# EM78P510_EM198810.net
KiCad netlist of a schematic drawn in Altium Designer
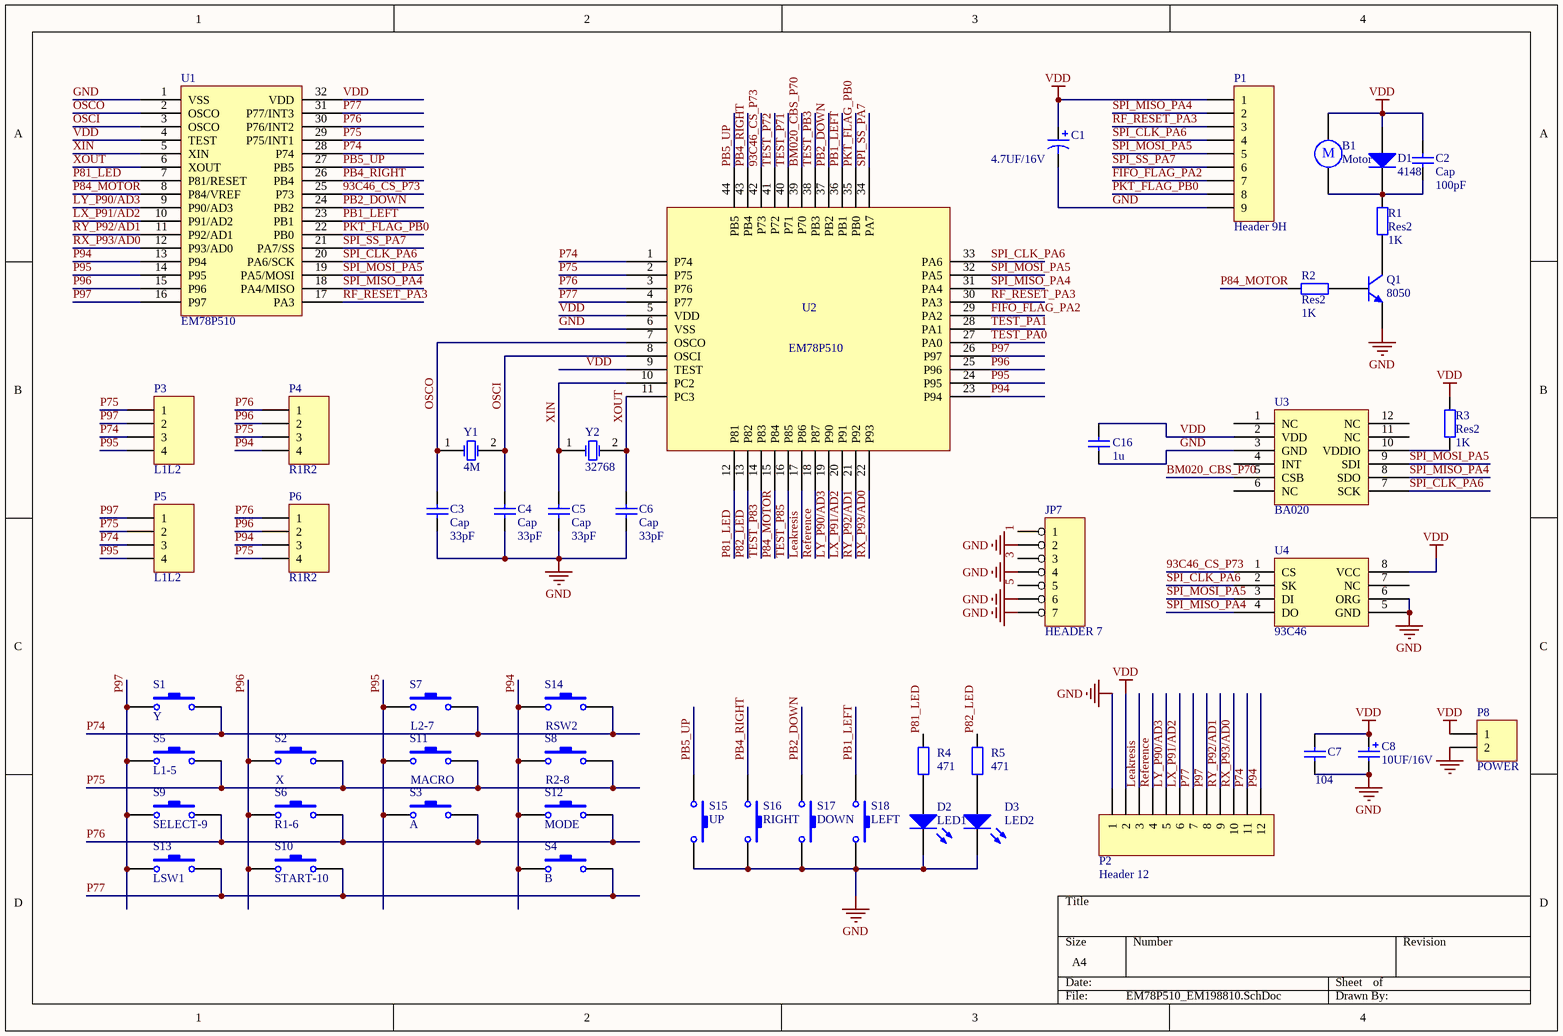
[diagram p0: EM78P510_EM198810.SchDoc]

(export (version "E")
  (design (tool "Eeschema 10.0.6"))
  (components
    (comp (ref "B1")
      (value "Motor")
      (footprint "sip2")
      (description "Motor, General Kind")
      (fields (field (name "PUBLISHER") "Altium Limited"))
      (libsource (lib "Miscellaneous Devices") (part "Motor"))
    )
    (comp (ref "C1")
      (value "4.7UF/16V")
      (footprint "c1206-2")
      (description "Polarized Capacitor (Radial)")
      (fields (field (name "Comment") "Cap Pol1") (field (name "PUBLISHER") "Altium Limited"))
      (libsource (lib "Miscellaneous Devices") (part "Cap Pol1"))
    )
    (comp (ref "C2")
      (value "Cap")
      (footprint "c0805")
      (description "Capacitor")
      (fields (field (name "ALTIUM_VALUE") "100pF") (field (name "PUBLISHER") "Altium Limited"))
      (libsource (lib "Miscellaneous Devices") (part "Cap"))
    )
    (comp (ref "C3")
      (value "Cap")
      (footprint "c0805")
      (description "Capacitor")
      (fields (field (name "ALTIUM_VALUE") "33pF") (field (name "PUBLISHER") "Altium Limited"))
      (libsource (lib "Miscellaneous Devices") (part "Cap"))
    )
    (comp (ref "C4")
      (value "Cap")
      (footprint "c0805")
      (description "Capacitor")
      (fields (field (name "ALTIUM_VALUE") "33pF") (field (name "PUBLISHER") "Altium Limited"))
      (libsource (lib "Miscellaneous Devices") (part "Cap"))
    )
    (comp (ref "C5")
      (value "Cap")
      (footprint "c0805")
      (description "Capacitor")
      (fields (field (name "ALTIUM_VALUE") "33pF") (field (name "PUBLISHER") "Altium Limited"))
      (libsource (lib "Miscellaneous Devices") (part "Cap"))
    )
    (comp (ref "C6")
      (value "Cap")
      (footprint "c0805")
      (description "Capacitor")
      (fields (field (name "ALTIUM_VALUE") "33pF") (field (name "PUBLISHER") "Altium Limited"))
      (libsource (lib "Miscellaneous Devices") (part "Cap"))
    )
    (comp (ref "C7")
      (value "104")
      (footprint "C0805")
      (description "Capacitor")
      (fields (field (name "Comment") "Cap") (field (name "PUBLISHER") "Altium Limited"))
      (libsource (lib "Miscellaneous Devices") (part "Cap"))
    )
    (comp (ref "C8")
      (value "10UF/16V")
      (footprint "RB5")
      (description "Polarized Capacitor (Radial)")
      (fields (field (name "Comment") "Cap Pol1") (field (name "PUBLISHER") "Altium Limited"))
      (libsource (lib "EM78P510_EM78M611_EM198810") (part "Cap Pol1"))
    )
    (comp (ref "C16")
      (value "1u")
      (footprint "C0805")
      (description "Capacitor")
      (fields (field (name "Comment") "Cap") (field (name "PUBLISHER") "Altium Limited"))
      (libsource (lib "Miscellaneous Devices") (part "Cap"))
    )
    (comp (ref "D1")
      (value "4148")
      (footprint "d1407")
      (description "Default Diode")
      (fields (field (name "PUBLISHER") "Altium Limited"))
      (libsource (lib "Miscellaneous Devices") (part "Diode"))
    )
    (comp (ref "D2")
      (value "LED1")
      (footprint "led-3")
      (description "Typical INFRARED GaAs LED")
      (fields (field (name "PUBLISHER") "Altium Limited"))
      (libsource (lib "Miscellaneous Devices") (part "LED0"))
    )
    (comp (ref "D3")
      (value "LED2")
      (footprint "led-3")
      (description "Typical INFRARED GaAs LED")
      (fields (field (name "PUBLISHER") "Altium Limited"))
      (libsource (lib "Miscellaneous Devices") (part "LED0"))
    )
    (comp (ref "JP7") (value "HEADER 7") (footprint "CON5") (libsource (lib "雨点元件") (part "HEADER 7")))
    (comp (ref "P1")
      (value "Header 9H")
      (footprint "rfm")
      (description "Header, 9-Pin, Right Angle")
      (fields (field (name "PUBLISHER") "Altium Limited"))
      (libsource (lib "Miscellaneous Connectors") (part "Header 9H"))
    )
    (comp (ref "P2")
      (value "Header 12")
      (footprint "SIP12")
      (description "Header, 12-Pin")
      (fields (field (name "PUBLISHER") "Altium Limited"))
      (libsource (lib "Miscellaneous Connectors") (part "Header 12"))
    )
    (comp (ref "P3")
      (value "L1L2")
      (footprint "SIP4")
      (description "Header, 4-Pin")
      (fields (field (name "PUBLISHER") "Altium Limited"))
      (libsource (lib "Miscellaneous Connectors") (part "Header 4"))
    )
    (comp (ref "P4")
      (value "R1R2")
      (footprint "SIP4")
      (description "Header, 4-Pin")
      (fields (field (name "PUBLISHER") "Altium Limited"))
      (libsource (lib "Miscellaneous Connectors") (part "Header 4"))
    )
    (comp (ref "P5")
      (value "L1L2")
      (footprint "SIP4")
      (description "Header, 4-Pin")
      (fields (field (name "PUBLISHER") "Altium Limited"))
      (libsource (lib "Miscellaneous Connectors") (part "Header 4"))
    )
    (comp (ref "P6")
      (value "R1R2")
      (footprint "SIP4")
      (description "Header, 4-Pin")
      (fields (field (name "PUBLISHER") "Altium Limited"))
      (libsource (lib "Miscellaneous Connectors") (part "Header 4"))
    )
    (comp (ref "P8")
      (value "POWER")
      (footprint "SIP2")
      (description "Header, 2-Pin")
      (fields (field (name "PUBLISHER") "Altium Limited"))
      (libsource (lib "Miscellaneous Connectors") (part "Header 2"))
    )
    (comp (ref "Q1")
      (value "8050")
      (footprint "sot-23")
      (description "NPN Bipolar Transistor")
      (fields (field (name "PUBLISHER") "Altium Limited"))
      (libsource (lib "Miscellaneous Devices") (part "NPN"))
    )
    (comp (ref "R1")
      (value "Res2")
      (footprint "r0805")
      (description "Resistor")
      (fields (field (name "ALTIUM_VALUE") "1K") (field (name "PUBLISHER") "Altium Limited"))
      (libsource (lib "Miscellaneous Devices") (part "Res2"))
    )
    (comp (ref "R2")
      (value "Res2")
      (footprint "r0805")
      (description "Resistor")
      (fields (field (name "ALTIUM_VALUE") "1K") (field (name "PUBLISHER") "Altium Limited"))
      (libsource (lib "") (part "Res2_1"))
    )
    (comp (ref "R3")
      (value "Res2")
      (footprint "r0805")
      (description "Resistor")
      (fields (field (name "ALTIUM_VALUE") "1K") (field (name "PUBLISHER") "Altium Limited"))
      (libsource (lib "Miscellaneous Devices") (part "Res2"))
    )
    (comp (ref "R4")
      (value "471")
      (footprint "r0805")
      (description "Resistor")
      (fields (field (name "Comment") "Res2") (field (name "PUBLISHER") "Altium Limited"))
      (libsource (lib "Miscellaneous Devices") (part "Res2"))
    )
    (comp (ref "R5")
      (value "471")
      (footprint "r0805")
      (description "Resistor")
      (fields (field (name "Comment") "Res2") (field (name "PUBLISHER") "Altium Limited"))
      (libsource (lib "Miscellaneous Devices") (part "Res2"))
    )
    (comp (ref "S1")
      (value "Y")
      (footprint "KeyPad1")
      (description "Switch")
      (fields (field (name "PUBLISHER") "Altium Limited"))
      (libsource (lib "EM78P510_EM78M611_EM198810_1") (part "SW-PB"))
    )
    (comp (ref "S2")
      (value "X")
      (footprint "KeyPad1")
      (description "Switch")
      (fields (field (name "PUBLISHER") "Altium Limited"))
      (libsource (lib "EM78P510_EM78M611_EM198810_1") (part "SW-PB"))
    )
    (comp (ref "S3")
      (value "A")
      (footprint "KeyPad1")
      (description "Switch")
      (fields (field (name "PUBLISHER") "Altium Limited"))
      (libsource (lib "EM78P510_EM78M611_EM198810_1") (part "SW-PB"))
    )
    (comp (ref "S4")
      (value "B")
      (footprint "KeyPad1")
      (description "Switch")
      (fields (field (name "PUBLISHER") "Altium Limited"))
      (libsource (lib "EM78P510_EM78M611_EM198810_1") (part "SW-PB"))
    )
    (comp (ref "S5")
      (value "L1-5")
      (footprint "KeyPad1")
      (description "Switch")
      (fields (field (name "PUBLISHER") "Altium Limited"))
      (libsource (lib "EM78P510_EM78M611_EM198810_1") (part "SW-PB"))
    )
    (comp (ref "S6")
      (value "R1-6")
      (footprint "KeyPad1")
      (description "Switch")
      (fields (field (name "PUBLISHER") "Altium Limited"))
      (libsource (lib "EM78P510_EM78M611_EM198810_1") (part "SW-PB"))
    )
    (comp (ref "S7")
      (value "L2-7")
      (footprint "KeyPad1")
      (description "Switch")
      (fields (field (name "PUBLISHER") "Altium Limited"))
      (libsource (lib "EM78P510_EM78M611_EM198810_1") (part "SW-PB"))
    )
    (comp (ref "S8")
      (value "R2-8")
      (footprint "KeyPad1")
      (description "Switch")
      (fields (field (name "PUBLISHER") "Altium Limited"))
      (libsource (lib "EM78P510_EM78M611_EM198810_1") (part "SW-PB"))
    )
    (comp (ref "S9")
      (value "SELECT-9")
      (footprint "KeyPad2")
      (description "Switch")
      (fields (field (name "PUBLISHER") "Altium Limited"))
      (libsource (lib "EM78P510_EM78M611_EM198810_1") (part "SW-PB"))
    )
    (comp (ref "S10")
      (value "START-10")
      (footprint "KeyPad2")
      (description "Switch")
      (fields (field (name "PUBLISHER") "Altium Limited"))
      (libsource (lib "EM78P510_EM78M611_EM198810_1") (part "SW-PB"))
    )
    (comp (ref "S11")
      (value "MACRO")
      (footprint "KeyPad2")
      (description "Switch")
      (fields (field (name "PUBLISHER") "Altium Limited"))
      (libsource (lib "EM78P510_EM78M611_EM198810_1") (part "SW-PB"))
    )
    (comp (ref "S12")
      (value "MODE")
      (footprint "KeyPad2")
      (description "Switch")
      (fields (field (name "PUBLISHER") "Altium Limited"))
      (libsource (lib "EM78P510_EM78M611_EM198810_1") (part "SW-PB"))
    )
    (comp (ref "S13")
      (value "LSW1")
      (footprint "KeyPad1")
      (description "Switch")
      (fields (field (name "PUBLISHER") "Altium Limited"))
      (libsource (lib "EM78P510_EM78M611_EM198810_1") (part "SW-PB"))
    )
    (comp (ref "S14")
      (value "RSW2")
      (footprint "KeyPad1")
      (description "Switch")
      (fields (field (name "PUBLISHER") "Altium Limited"))
      (libsource (lib "EM78P510_EM78M611_EM198810_1") (part "SW-PB"))
    )
    (comp (ref "S15")
      (value "UP")
      (footprint "KeyPad1")
      (description "Switch")
      (fields (field (name "PUBLISHER") "Altium Limited"))
      (libsource (lib "EM78P510_EM78M611_EM198810_1") (part "SW-PB"))
    )
    (comp (ref "S16")
      (value "RIGHT")
      (footprint "KeyPad1")
      (description "Switch")
      (fields (field (name "PUBLISHER") "Altium Limited"))
      (libsource (lib "EM78P510_EM78M611_EM198810_1") (part "SW-PB"))
    )
    (comp (ref "S17")
      (value "DOWN")
      (footprint "KeyPad1")
      (description "Switch")
      (fields (field (name "PUBLISHER") "Altium Limited"))
      (libsource (lib "EM78P510_EM78M611_EM198810_1") (part "SW-PB"))
    )
    (comp (ref "S18")
      (value "LEFT")
      (footprint "KeyPad1")
      (description "Switch")
      (fields (field (name "PUBLISHER") "Altium Limited"))
      (libsource (lib "EM78P510_EM78M611_EM198810_1") (part "SW-PB"))
    )
    (comp (ref "U1") (value "EM78P510") (libsource (lib "Schlib1") (part "EM78P510-32")))
    (comp (ref "U2") (value "EM78P510") (libsource (lib "Schlib1") (part "EM78P510-44")))
    (comp (ref "U3") (value "BA020") (footprint "lcc12") (libsource (lib "Schlib1") (part "BA020")))
    (comp (ref "U4") (value "93C46") (footprint "sop8") (libsource (lib "Schlib1") (part "93C46")))
    (comp (ref "Y1")
      (value "4M")
      (footprint "XTAL1")
      (description "Crystal Oscillator")
      (fields (field (name "PUBLISHER") "Altium Limited"))
      (libsource (lib "Miscellaneous Devices") (part "XTAL"))
    )
    (comp (ref "Y2")
      (value "32768")
      (footprint "XTAL2")
      (description "Crystal Oscillator")
      (fields (field (name "PUBLISHER") "Altium Limited"))
      (libsource (lib "Miscellaneous Devices") (part "XTAL"))
    )
  )
  (nets
    (net (code "1") (name "/1") (class "Default")
      (node (ref "JP7") (pin "1") (pinfunction "1_1") (pintype "passive"))
    )
    (net (code "2") (name "/3") (class "Default")
      (node (ref "JP7") (pin "3") (pinfunction "3_3") (pintype "passive"))
    )
    (net (code "3") (name "/5") (class "Default")
      (node (ref "JP7") (pin "5") (pinfunction "5_5") (pintype "passive"))
    )
    (net (code "4") (name "/93C46_CS_P73") (class "Default")
      (node (ref "U1") (pin "25") (pinfunction "P73_25") (pintype "passive"))
      (node (ref "U2") (pin "42") (pinfunction "P73_42") (pintype "passive"))
      (node (ref "U4") (pin "1") (pinfunction "CS_1") (pintype "passive"))
    )
    (net (code "5") (name "/BM020_CBS_P70") (class "Default")
      (node (ref "U2") (pin "39") (pinfunction "P70_39") (pintype "passive"))
      (node (ref "U3") (pin "5") (pinfunction "CSB_5") (pintype "passive"))
    )
    (net (code "6") (name "/FIFO_FLAG_PA2") (class "Default")
      (node (ref "P1") (pin "7") (pinfunction "7_7") (pintype "passive"))
      (node (ref "U2") (pin "29") (pinfunction "PA2_29") (pintype "passive"))
    )
    (net (code "7") (name "/LX_P91{slash}AD2") (class "Default")
      (node (ref "P2") (pin "6") (pinfunction "6_6") (pintype "passive"))
      (node (ref "U1") (pin "10") (pinfunction "P91/AD2_10") (pintype "passive"))
      (node (ref "U2") (pin "20") (pinfunction "P91_20") (pintype "passive"))
    )
    (net (code "8") (name "/LY_P90{slash}AD3") (class "Default")
      (node (ref "P2") (pin "5") (pinfunction "5_5") (pintype "passive"))
      (node (ref "U1") (pin "9") (pinfunction "P90/AD3_9") (pintype "passive"))
      (node (ref "U2") (pin "19") (pinfunction "P90_19") (pintype "passive"))
    )
    (net (code "9") (name "/Leakresis") (class "Default")
      (node (ref "P2") (pin "3") (pinfunction "3_3") (pintype "passive"))
      (node (ref "U2") (pin "17") (pinfunction "P86_17") (pintype "passive"))
    )
    (net (code "10") (name "/OSCI") (class "Default")
      (node (ref "C4") (pin "2") (pinfunction "2_2") (pintype "passive"))
      (node (ref "U1") (pin "3") (pinfunction "OSCO_3") (pintype "passive"))
      (node (ref "U2") (pin "8") (pinfunction "OSCI_8") (pintype "passive"))
      (node (ref "Y1") (pin "2") (pinfunction "OSC2_2") (pintype "passive"))
    )
    (net (code "11") (name "/OSCO") (class "Default")
      (node (ref "C3") (pin "2") (pinfunction "2_2") (pintype "passive"))
      (node (ref "U1") (pin "2") (pinfunction "OSCO_2") (pintype "passive"))
      (node (ref "U2") (pin "7") (pinfunction "OSCO_7") (pintype "passive"))
      (node (ref "Y1") (pin "1") (pinfunction "OSC1_1") (pintype "passive"))
    )
    (net (code "12") (name "/P74") (class "Default")
      (node (ref "P2") (pin "11") (pinfunction "11_11") (pintype "passive"))
      (node (ref "P3") (pin "3") (pinfunction "3_3") (pintype "passive"))
      (node (ref "P5") (pin "3") (pinfunction "3_3") (pintype "passive"))
      (node (ref "S1") (pin "2") (pinfunction "2_2") (pintype "passive"))
      (node (ref "S14") (pin "2") (pinfunction "2_2") (pintype "passive"))
      (node (ref "S7") (pin "2") (pinfunction "2_2") (pintype "passive"))
      (node (ref "U1") (pin "28") (pinfunction "P74_28") (pintype "passive"))
      (node (ref "U2") (pin "1") (pinfunction "P74_1") (pintype "passive"))
    )
    (net (code "13") (name "/P75") (class "Default")
      (node (ref "P3") (pin "1") (pinfunction "1_1") (pintype "passive"))
      (node (ref "P4") (pin "3") (pinfunction "3_3") (pintype "passive"))
      (node (ref "P5") (pin "2") (pinfunction "2_2") (pintype "passive"))
      (node (ref "P6") (pin "4") (pinfunction "4_4") (pintype "passive"))
      (node (ref "S11") (pin "2") (pinfunction "2_2") (pintype "passive"))
      (node (ref "S2") (pin "2") (pinfunction "2_2") (pintype "passive"))
      (node (ref "S5") (pin "2") (pinfunction "2_2") (pintype "passive"))
      (node (ref "S8") (pin "2") (pinfunction "2_2") (pintype "passive"))
      (node (ref "U1") (pin "29") (pinfunction "P75/INT1_29") (pintype "passive"))
      (node (ref "U2") (pin "2") (pinfunction "P75_2") (pintype "passive"))
    )
    (net (code "14") (name "/P76") (class "Default")
      (node (ref "P4") (pin "1") (pinfunction "1_1") (pintype "passive"))
      (node (ref "P6") (pin "1") (pinfunction "1_1") (pintype "passive"))
      (node (ref "S12") (pin "2") (pinfunction "2_2") (pintype "passive"))
      (node (ref "S3") (pin "2") (pinfunction "2_2") (pintype "passive"))
      (node (ref "S6") (pin "2") (pinfunction "2_2") (pintype "passive"))
      (node (ref "S9") (pin "2") (pinfunction "2_2") (pintype "passive"))
      (node (ref "U1") (pin "30") (pinfunction "P76/INT2_30") (pintype "passive"))
      (node (ref "U2") (pin "3") (pinfunction "P76_3") (pintype "passive"))
    )
    (net (code "15") (name "/P77") (class "Default")
      (node (ref "P2") (pin "7") (pinfunction "7_7") (pintype "passive"))
      (node (ref "S10") (pin "2") (pinfunction "2_2") (pintype "passive"))
      (node (ref "S13") (pin "2") (pinfunction "2_2") (pintype "passive"))
      (node (ref "S4") (pin "2") (pinfunction "2_2") (pintype "passive"))
      (node (ref "U1") (pin "31") (pinfunction "P77/INT3_31") (pintype "passive"))
      (node (ref "U2") (pin "4") (pinfunction "P77_4") (pintype "passive"))
    )
    (net (code "16") (name "/P81_LED") (class "Default")
      (node (ref "R4") (pin "1") (pinfunction "1_1") (pintype "passive"))
      (node (ref "U1") (pin "7") (pinfunction "P81/RESET_7") (pintype "passive"))
      (node (ref "U2") (pin "12") (pinfunction "P81_12") (pintype "passive"))
    )
    (net (code "17") (name "/P82_LED") (class "Default")
      (node (ref "R5") (pin "1") (pinfunction "1_1") (pintype "passive"))
      (node (ref "U2") (pin "13") (pinfunction "P82_13") (pintype "passive"))
    )
    (net (code "18") (name "/P84_MOTOR") (class "Default")
      (node (ref "R2") (pin "1") (pinfunction "1_1") (pintype "passive"))
      (node (ref "U1") (pin "8") (pinfunction "P84/VREF_8") (pintype "passive"))
      (node (ref "U2") (pin "15") (pinfunction "P84_15") (pintype "passive"))
    )
    (net (code "19") (name "/P94") (class "Default")
      (node (ref "P2") (pin "12") (pinfunction "12_12") (pintype "passive"))
      (node (ref "P4") (pin "4") (pinfunction "4_4") (pintype "passive"))
      (node (ref "P6") (pin "3") (pinfunction "3_3") (pintype "passive"))
      (node (ref "S12") (pin "1") (pinfunction "1_1") (pintype "passive"))
      (node (ref "S14") (pin "1") (pinfunction "1_1") (pintype "passive"))
      (node (ref "S4") (pin "1") (pinfunction "1_1") (pintype "passive"))
      (node (ref "S8") (pin "1") (pinfunction "1_1") (pintype "passive"))
      (node (ref "U1") (pin "13") (pinfunction "P94_13") (pintype "passive"))
      (node (ref "U2") (pin "23") (pinfunction "P94_23") (pintype "passive"))
    )
    (net (code "20") (name "/P95") (class "Default")
      (node (ref "P3") (pin "4") (pinfunction "4_4") (pintype "passive"))
      (node (ref "P5") (pin "4") (pinfunction "4_4") (pintype "passive"))
      (node (ref "S11") (pin "1") (pinfunction "1_1") (pintype "passive"))
      (node (ref "S3") (pin "1") (pinfunction "1_1") (pintype "passive"))
      (node (ref "S7") (pin "1") (pinfunction "1_1") (pintype "passive"))
      (node (ref "U1") (pin "14") (pinfunction "P95_14") (pintype "passive"))
      (node (ref "U2") (pin "24") (pinfunction "P95_24") (pintype "passive"))
    )
    (net (code "21") (name "/P96") (class "Default")
      (node (ref "P4") (pin "2") (pinfunction "2_2") (pintype "passive"))
      (node (ref "P6") (pin "2") (pinfunction "2_2") (pintype "passive"))
      (node (ref "S10") (pin "1") (pinfunction "1_1") (pintype "passive"))
      (node (ref "S2") (pin "1") (pinfunction "1_1") (pintype "passive"))
      (node (ref "S6") (pin "1") (pinfunction "1_1") (pintype "passive"))
      (node (ref "U1") (pin "15") (pinfunction "P96_15") (pintype "passive"))
      (node (ref "U2") (pin "25") (pinfunction "P96_25") (pintype "passive"))
    )
    (net (code "22") (name "/P97") (class "Default")
      (node (ref "P2") (pin "8") (pinfunction "8_8") (pintype "passive"))
      (node (ref "P3") (pin "2") (pinfunction "2_2") (pintype "passive"))
      (node (ref "P5") (pin "1") (pinfunction "1_1") (pintype "passive"))
      (node (ref "S1") (pin "1") (pinfunction "1_1") (pintype "passive"))
      (node (ref "S13") (pin "1") (pinfunction "1_1") (pintype "passive"))
      (node (ref "S5") (pin "1") (pinfunction "1_1") (pintype "passive"))
      (node (ref "S9") (pin "1") (pinfunction "1_1") (pintype "passive"))
      (node (ref "U1") (pin "16") (pinfunction "P97_16") (pintype "passive"))
      (node (ref "U2") (pin "26") (pinfunction "P97_26") (pintype "passive"))
    )
    (net (code "23") (name "/PB1_LEFT") (class "Default")
      (node (ref "S18") (pin "1") (pinfunction "1_1") (pintype "passive"))
      (node (ref "U1") (pin "23") (pinfunction "PB1_23") (pintype "passive"))
      (node (ref "U2") (pin "36") (pinfunction "PB1_36") (pintype "passive"))
    )
    (net (code "24") (name "/PB2_DOWN") (class "Default")
      (node (ref "S17") (pin "1") (pinfunction "1_1") (pintype "passive"))
      (node (ref "U1") (pin "24") (pinfunction "PB2_24") (pintype "passive"))
      (node (ref "U2") (pin "37") (pinfunction "PB2_37") (pintype "passive"))
    )
    (net (code "25") (name "/PB4_RIGHT") (class "Default")
      (node (ref "S16") (pin "1") (pinfunction "1_1") (pintype "passive"))
      (node (ref "U1") (pin "26") (pinfunction "PB4_26") (pintype "passive"))
      (node (ref "U2") (pin "43") (pinfunction "PB4_43") (pintype "passive"))
    )
    (net (code "26") (name "/PB5_UP") (class "Default")
      (node (ref "S15") (pin "1") (pinfunction "1_1") (pintype "passive"))
      (node (ref "U1") (pin "27") (pinfunction "PB5_27") (pintype "passive"))
      (node (ref "U2") (pin "44") (pinfunction "PB5_44") (pintype "passive"))
    )
    (net (code "27") (name "/PKT_FLAG_PB0") (class "Default")
      (node (ref "P1") (pin "8") (pinfunction "8_8") (pintype "passive"))
      (node (ref "U1") (pin "22") (pinfunction "PB0_22") (pintype "passive"))
      (node (ref "U2") (pin "35") (pinfunction "PB0_35") (pintype "passive"))
    )
    (net (code "28") (name "/RF_RESET_PA3") (class "Default")
      (node (ref "P1") (pin "3") (pinfunction "3_3") (pintype "passive"))
      (node (ref "U1") (pin "17") (pinfunction "PA3_17") (pintype "passive"))
      (node (ref "U2") (pin "30") (pinfunction "PA3_30") (pintype "passive"))
    )
    (net (code "29") (name "/RX_P93{slash}AD0") (class "Default")
      (node (ref "P2") (pin "10") (pinfunction "10_10") (pintype "passive"))
      (node (ref "U1") (pin "12") (pinfunction "P93/AD0_12") (pintype "passive"))
      (node (ref "U2") (pin "22") (pinfunction "P93_22") (pintype "passive"))
    )
    (net (code "30") (name "/RY_P92{slash}AD1") (class "Default")
      (node (ref "P2") (pin "9") (pinfunction "9_9") (pintype "passive"))
      (node (ref "U1") (pin "11") (pinfunction "P92/AD1_11") (pintype "passive"))
      (node (ref "U2") (pin "21") (pinfunction "P92_21") (pintype "passive"))
    )
    (net (code "31") (name "/Reference") (class "Default")
      (node (ref "P2") (pin "4") (pinfunction "4_4") (pintype "passive"))
      (node (ref "U2") (pin "18") (pinfunction "P87_18") (pintype "passive"))
    )
    (net (code "32") (name "/SPI_CLK_PA6") (class "Default")
      (node (ref "P1") (pin "4") (pinfunction "4_4") (pintype "passive"))
      (node (ref "U1") (pin "20") (pinfunction "PA6/SCK_20") (pintype "passive"))
      (node (ref "U2") (pin "33") (pinfunction "PA6_33") (pintype "passive"))
      (node (ref "U3") (pin "7") (pinfunction "SCK_7") (pintype "passive"))
      (node (ref "U4") (pin "2") (pinfunction "SK_2") (pintype "passive"))
    )
    (net (code "33") (name "/SPI_MISO_PA4") (class "Default")
      (node (ref "P1") (pin "2") (pinfunction "2_2") (pintype "passive"))
      (node (ref "U1") (pin "18") (pinfunction "PA4/MISO_18") (pintype "passive"))
      (node (ref "U2") (pin "31") (pinfunction "PA4_31") (pintype "passive"))
      (node (ref "U3") (pin "8") (pinfunction "SDO_8") (pintype "passive"))
      (node (ref "U4") (pin "4") (pinfunction "DO_4") (pintype "passive"))
    )
    (net (code "34") (name "/SPI_MOSI_PA5") (class "Default")
      (node (ref "P1") (pin "5") (pinfunction "5_5") (pintype "passive"))
      (node (ref "U1") (pin "19") (pinfunction "PA5/MOSI_19") (pintype "passive"))
      (node (ref "U2") (pin "32") (pinfunction "PA5_32") (pintype "passive"))
      (node (ref "U3") (pin "9") (pinfunction "SDI_9") (pintype "passive"))
      (node (ref "U4") (pin "3") (pinfunction "DI_3") (pintype "passive"))
    )
    (net (code "35") (name "/SPI_SS_PA7") (class "Default")
      (node (ref "P1") (pin "6") (pinfunction "6_6") (pintype "passive"))
      (node (ref "U1") (pin "21") (pinfunction "PA7/SS_21") (pintype "passive"))
      (node (ref "U2") (pin "34") (pinfunction "PA7_34") (pintype "passive"))
    )
    (net (code "36") (name "/TEST_P71") (class "Default")
      (node (ref "U2") (pin "40") (pinfunction "P71_40") (pintype "passive"))
    )
    (net (code "37") (name "/TEST_P72") (class "Default")
      (node (ref "U2") (pin "41") (pinfunction "P72_41") (pintype "passive"))
    )
    (net (code "38") (name "/TEST_P83") (class "Default")
      (node (ref "U2") (pin "14") (pinfunction "P83_14") (pintype "passive"))
    )
    (net (code "39") (name "/TEST_P85") (class "Default")
      (node (ref "U2") (pin "16") (pinfunction "P85_16") (pintype "passive"))
    )
    (net (code "40") (name "/TEST_PA0") (class "Default")
      (node (ref "U2") (pin "27") (pinfunction "PA0_27") (pintype "passive"))
    )
    (net (code "41") (name "/TEST_PA1") (class "Default")
      (node (ref "U2") (pin "28") (pinfunction "PA1_28") (pintype "passive"))
    )
    (net (code "42") (name "/TEST_PB3") (class "Default")
      (node (ref "U2") (pin "38") (pinfunction "PB3_38") (pintype "passive"))
    )
    (net (code "43") (name "/XIN") (class "Default")
      (node (ref "C5") (pin "2") (pinfunction "2_2") (pintype "passive"))
      (node (ref "U1") (pin "5") (pinfunction "XIN_5") (pintype "passive"))
      (node (ref "U2") (pin "10") (pinfunction "PC2_10") (pintype "passive"))
      (node (ref "Y2") (pin "1") (pinfunction "OSC1_1") (pintype "passive"))
    )
    (net (code "44") (name "/XOUT") (class "Default")
      (node (ref "C6") (pin "2") (pinfunction "2_2") (pintype "passive"))
      (node (ref "U1") (pin "6") (pinfunction "XOUT_6") (pintype "passive"))
      (node (ref "U2") (pin "11") (pinfunction "PC3_11") (pintype "passive"))
      (node (ref "Y2") (pin "2") (pinfunction "OSC2_2") (pintype "passive"))
    )
    (net (code "45") (name "GND") (class "Default")
      (node (ref "C1") (pin "2") (pinfunction "2_2") (pintype "passive"))
      (node (ref "C16") (pin "1") (pinfunction "1_1") (pintype "passive"))
      (node (ref "C3") (pin "1") (pinfunction "1_1") (pintype "passive"))
      (node (ref "C4") (pin "1") (pinfunction "1_1") (pintype "passive"))
      (node (ref "C5") (pin "1") (pinfunction "1_1") (pintype "passive"))
      (node (ref "C6") (pin "1") (pinfunction "1_1") (pintype "passive"))
      (node (ref "C7") (pin "1") (pinfunction "1_1") (pintype "passive"))
      (node (ref "C8") (pin "2") (pinfunction "2_2") (pintype "passive"))
      (node (ref "D2") (pin "2") (pinfunction "K_2") (pintype "passive"))
      (node (ref "D3") (pin "2") (pinfunction "K_2") (pintype "passive"))
      (node (ref "JP7") (pin "2") (pinfunction "2_2") (pintype "passive"))
      (node (ref "JP7") (pin "4") (pinfunction "4_4") (pintype "passive"))
      (node (ref "JP7") (pin "6") (pinfunction "6_6") (pintype "passive"))
      (node (ref "JP7") (pin "7") (pinfunction "7_7") (pintype "passive"))
      (node (ref "P1") (pin "9") (pinfunction "9_9") (pintype "passive"))
      (node (ref "P2") (pin "1") (pinfunction "1_1") (pintype "passive"))
      (node (ref "P8") (pin "2") (pinfunction "2_2") (pintype "passive"))
      (node (ref "Q1") (pin "3") (pinfunction "E_3") (pintype "passive"))
      (node (ref "S15") (pin "2") (pinfunction "2_2") (pintype "passive"))
      (node (ref "S16") (pin "2") (pinfunction "2_2") (pintype "passive"))
      (node (ref "S17") (pin "2") (pinfunction "2_2") (pintype "passive"))
      (node (ref "S18") (pin "2") (pinfunction "2_2") (pintype "passive"))
      (node (ref "U1") (pin "1") (pinfunction "VSS_1") (pintype "passive"))
      (node (ref "U2") (pin "6") (pinfunction "VSS_6") (pintype "passive"))
      (node (ref "U3") (pin "3") (pinfunction "GND_3") (pintype "passive"))
      (node (ref "U4") (pin "5") (pinfunction "GND_5") (pintype "passive"))
      (node (ref "U4") (pin "6") (pinfunction "ORG_6") (pintype "passive"))
    )
    (net (code "46") (name "Net-(D1-K)") (class "Default")
      (node (ref "B1") (pin "2") (pinfunction "2_2") (pintype "passive"))
      (node (ref "C2") (pin "1") (pinfunction "1_1") (pintype "passive"))
      (node (ref "D1") (pin "2") (pinfunction "K_2") (pintype "passive"))
      (node (ref "R1") (pin "1") (pinfunction "1_1") (pintype "passive"))
    )
    (net (code "47") (name "Net-(D2-A)") (class "Default")
      (node (ref "D2") (pin "1") (pinfunction "A_1") (pintype "passive"))
      (node (ref "R4") (pin "2") (pinfunction "2_2") (pintype "passive"))
    )
    (net (code "48") (name "Net-(D3-A)") (class "Default")
      (node (ref "D3") (pin "1") (pinfunction "A_1") (pintype "passive"))
      (node (ref "R5") (pin "2") (pinfunction "2_2") (pintype "passive"))
    )
    (net (code "49") (name "Net-(Q1-B)") (class "Default")
      (node (ref "Q1") (pin "2") (pinfunction "B_2") (pintype "passive"))
      (node (ref "R2") (pin "2") (pinfunction "2_2") (pintype "passive"))
    )
    (net (code "50") (name "Net-(Q1-C)") (class "Default")
      (node (ref "Q1") (pin "1") (pinfunction "C_1") (pintype "passive"))
      (node (ref "R1") (pin "2") (pinfunction "2_2") (pintype "passive"))
    )
    (net (code "51") (name "Net-(U3-VDDIO)") (class "Default")
      (node (ref "R3") (pin "2") (pinfunction "2_2") (pintype "passive"))
      (node (ref "U3") (pin "10") (pinfunction "VDDIO_10") (pintype "passive"))
    )
    (net (code "52") (name "VDD") (class "Default")
      (node (ref "B1") (pin "1") (pinfunction "1_1") (pintype "passive"))
      (node (ref "C1") (pin "1") (pinfunction "1_1") (pintype "passive"))
      (node (ref "C16") (pin "2") (pinfunction "2_2") (pintype "passive"))
      (node (ref "C2") (pin "2") (pinfunction "2_2") (pintype "passive"))
      (node (ref "C7") (pin "2") (pinfunction "2_2") (pintype "passive"))
      (node (ref "C8") (pin "1") (pinfunction "1_1") (pintype "passive"))
      (node (ref "D1") (pin "1") (pinfunction "A_1") (pintype "passive"))
      (node (ref "P1") (pin "1") (pinfunction "1_1") (pintype "passive"))
      (node (ref "P2") (pin "2") (pinfunction "2_2") (pintype "passive"))
      (node (ref "P8") (pin "1") (pinfunction "1_1") (pintype "passive"))
      (node (ref "R3") (pin "1") (pinfunction "1_1") (pintype "passive"))
      (node (ref "U1") (pin "32") (pinfunction "VDD_32") (pintype "passive"))
      (node (ref "U1") (pin "4") (pinfunction "TEST_4") (pintype "passive"))
      (node (ref "U2") (pin "5") (pinfunction "VDD_5") (pintype "passive"))
      (node (ref "U2") (pin "9") (pinfunction "TEST_9") (pintype "passive"))
      (node (ref "U3") (pin "2") (pinfunction "VDD_2") (pintype "passive"))
      (node (ref "U4") (pin "8") (pinfunction "VCC_8") (pintype "passive"))
    )
    (net (code "53") (name "unconnected-(U3-INT-Pad4)") (class "Default")
      (node (ref "U3") (pin "4") (pinfunction "INT_4") (pintype "passive"))
    )
    (net (code "54") (name "unconnected-(U3-NC-Pad1)") (class "Default")
      (node (ref "U3") (pin "1") (pinfunction "NC_1") (pintype "passive"))
    )
    (net (code "55") (name "unconnected-(U3-NC-Pad6)") (class "Default")
      (node (ref "U3") (pin "6") (pinfunction "NC_6") (pintype "passive"))
    )
    (net (code "56") (name "unconnected-(U3-NC-Pad11)") (class "Default")
      (node (ref "U3") (pin "11") (pinfunction "NC_11") (pintype "passive"))
    )
    (net (code "57") (name "unconnected-(U3-NC-Pad12)") (class "Default")
      (node (ref "U3") (pin "12") (pinfunction "NC_12") (pintype "passive"))
    )
    (net (code "58") (name "unconnected-(U4-NC-Pad7)") (class "Default")
      (node (ref "U4") (pin "7") (pinfunction "NC_7") (pintype "passive"))
    )
  )
)
